# microcontroller_board2.net
KiCad netlist of a schematic drawn in Altium Designer
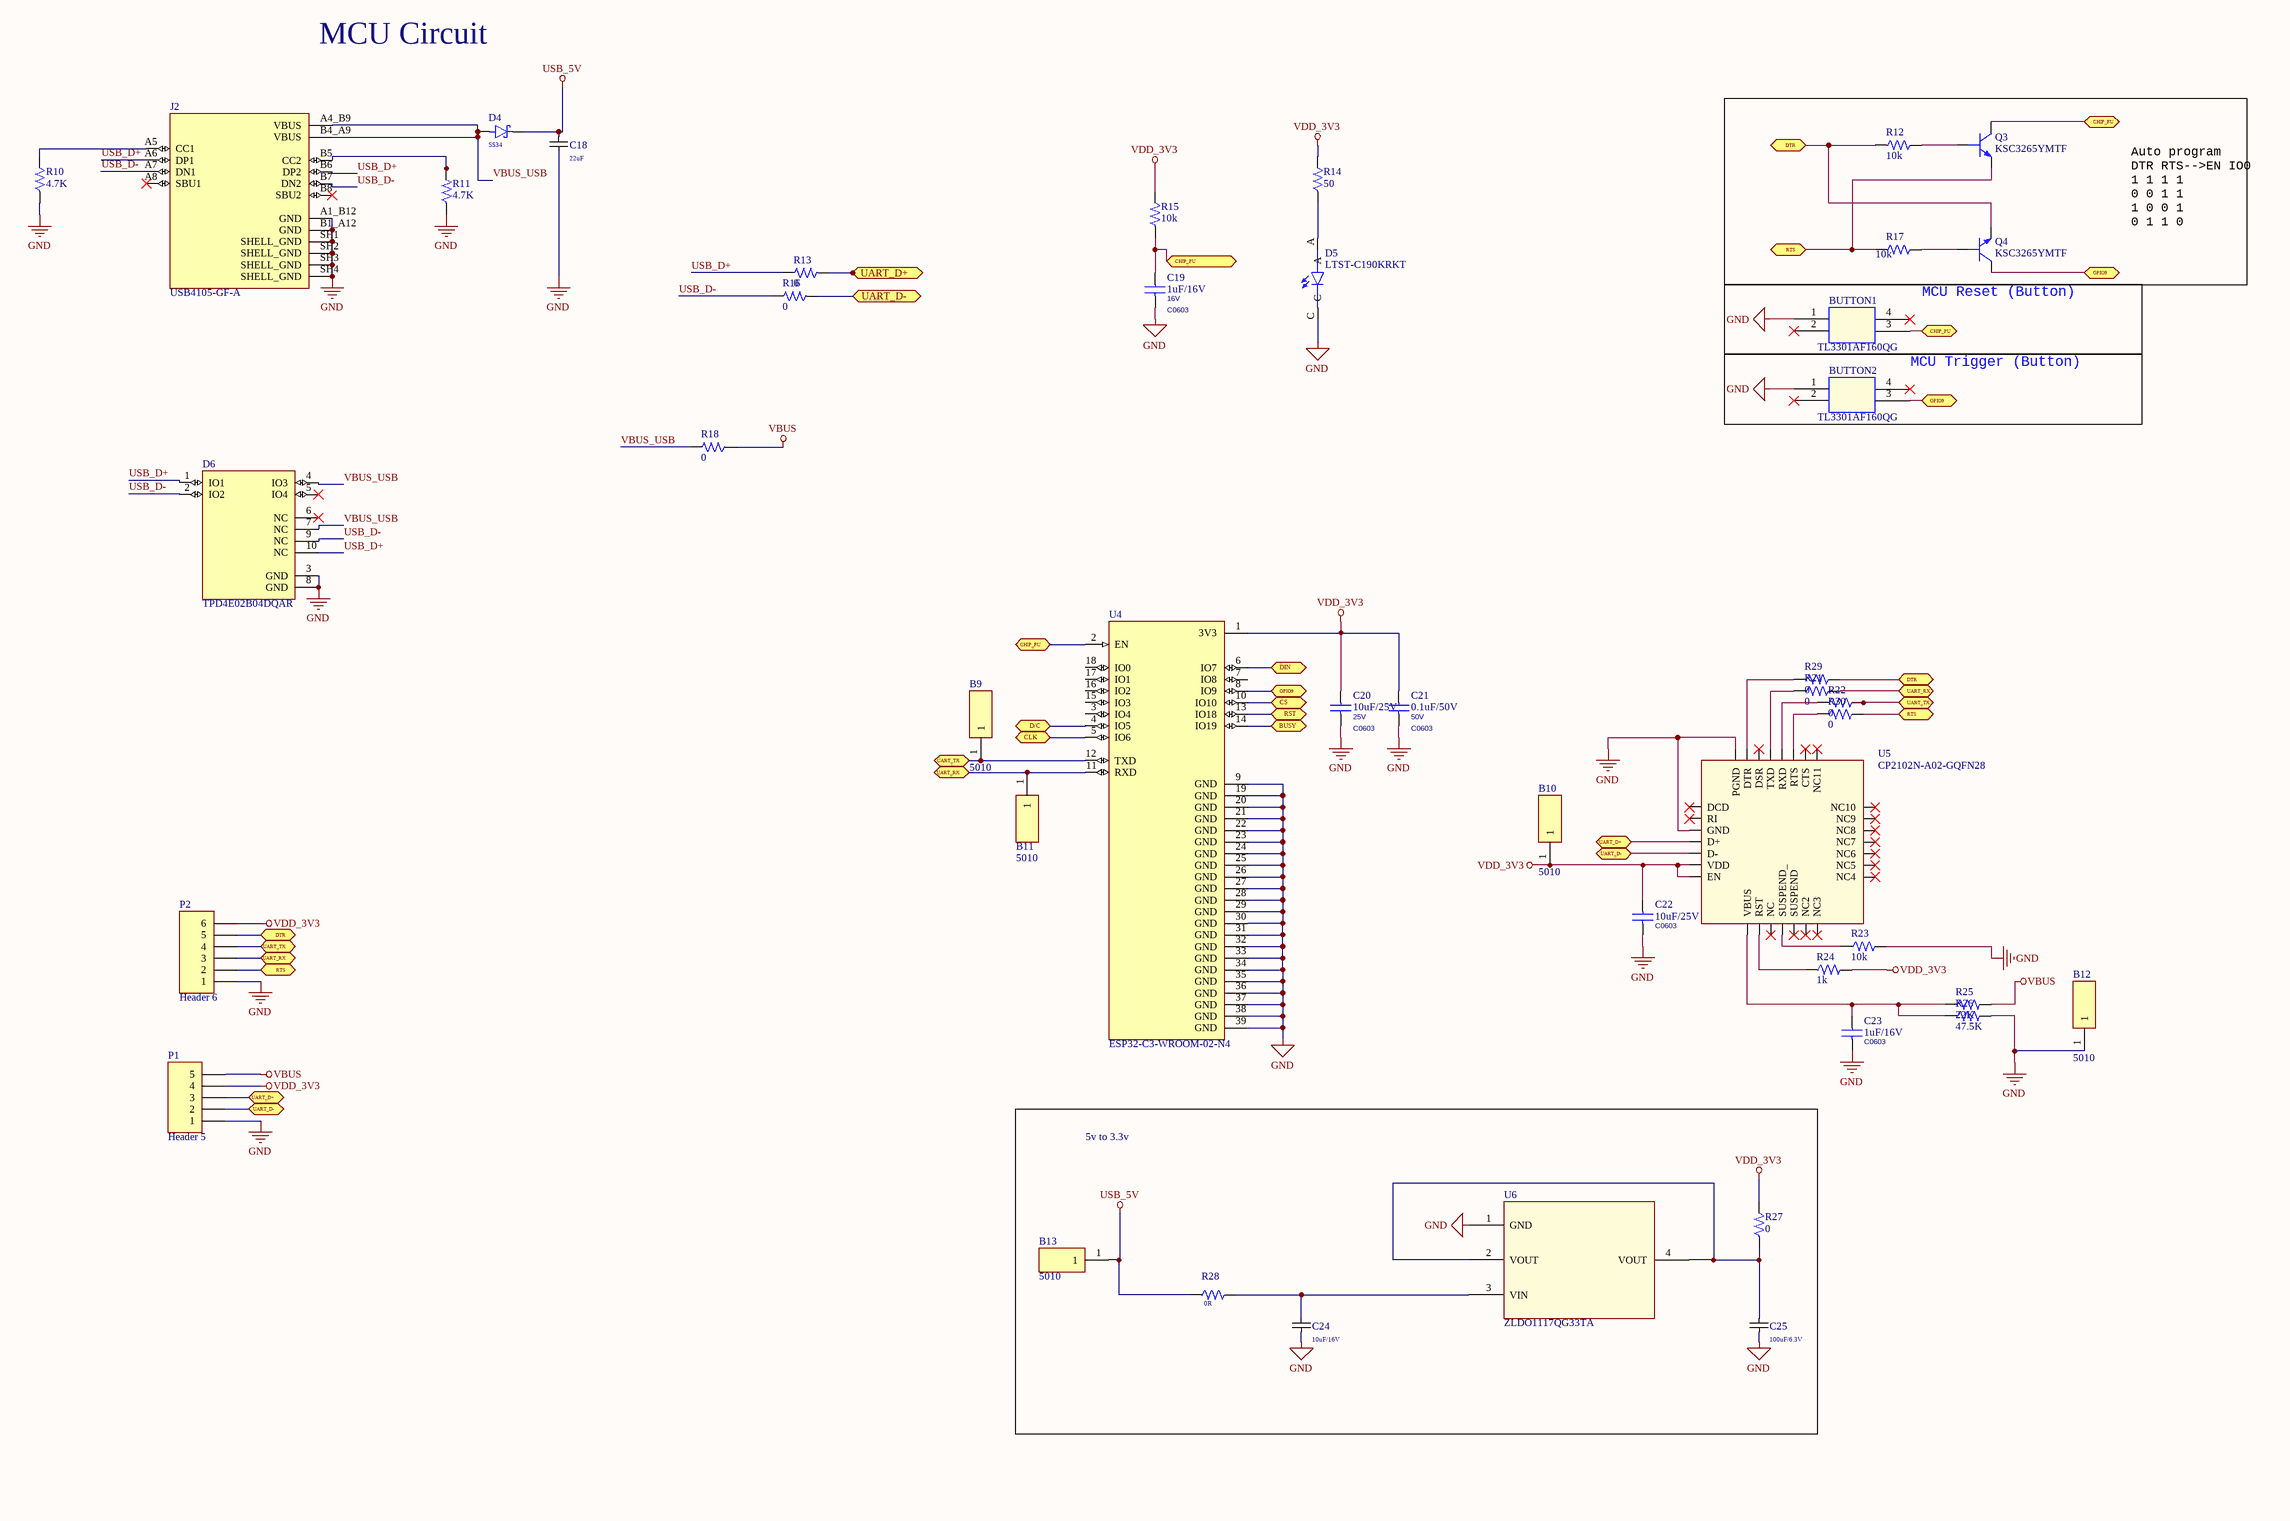
[diagram p0: microcontroller_board2.SchDoc]

(export (version "E")
  (design (tool "Eeschema 10.0.6"))
  (components
    (comp (ref "B9")
      (value "5010")
      (footprint "5010")
      (description "KEYSTONE - 5010 - TEST POINT, PCB, THROUGH HOLE")
      (fields (field (name "MOUSER PART NUMBER") "534-5010"))
      (libsource (lib "") (part "5010_1"))
    )
    (comp (ref "B10")
      (value "5010")
      (footprint "5010")
      (description "KEYSTONE - 5010 - TEST POINT, PCB, THROUGH HOLE")
      (fields (field (name "MOUSER PART NUMBER") "534-5010"))
      (libsource (lib "") (part "5010_1"))
    )
    (comp (ref "B11")
      (value "5010")
      (footprint "5010")
      (description "KEYSTONE - 5010 - TEST POINT, PCB, THROUGH HOLE")
      (fields (field (name "MOUSER PART NUMBER") "534-5010"))
      (libsource (lib "Schlib1") (part "5010"))
    )
    (comp (ref "B12")
      (value "5010")
      (footprint "5010")
      (description "KEYSTONE - 5010 - TEST POINT, PCB, THROUGH HOLE")
      (fields (field (name "MOUSER PART NUMBER") "534-5010"))
      (libsource (lib "") (part "5010_1"))
    )
    (comp (ref "B13")
      (value "5010")
      (footprint "5010")
      (description "KEYSTONE - 5010 - TEST POINT, PCB, THROUGH HOLE")
      (fields (field (name "MOUSER PART NUMBER") "534-5010"))
      (libsource (lib "R41") (part "5010"))
    )
    (comp (ref "BUTTON1")
      (value "TL3301AF160QG")
      (footprint "TL3301AF160QG")
      (libsource (lib "*") (part "CON4AP_0"))
    )
    (comp (ref "BUTTON2")
      (value "TL3301AF160QG")
      (footprint "TL3301AF160QG")
      (libsource (lib "*") (part "CON4AP_0"))
    )
    (comp (ref "C18")
      (value "22uF")
      (footprint "Cap_0805")
      (description "810-C2012X5R1V226MAC")
      (fields (field (name "MP") "C2012X5R1V226M125AC"))
      (libsource (lib "LRC_Components") (part "CAP_0805"))
    )
    (comp (ref "C19")
      (value "1uF/16V")
      (footprint "Cap_0603")
      (fields
        (field (name "PCB FOOTPRINT") "C0603")
        (field (name "PART NUMBER") "NC_0102-1422C12")
        (field (name "MANUFACTURER") "Murata")
        (field (name "TOLERANCE") "¡Ó10%")
        (field (name "VOLTAGE") "16V")
      )
      (libsource (lib "*") (part "CAP NP_Dup2"))
    )
    (comp (ref "C20")
      (value "10uF/25V")
      (footprint "Cap_0603")
      (fields
        (field (name "PART NUMBER") "NC_0102-1422C12")
        (field (name "MANUFACTURER") "Murata")
        (field (name "TOLERANCE") "¡Ó10%")
        (field (name "VOLTAGE") "25V")
        (field (name "PCB FOOTPRINT") "C0603")
      )
      (libsource (lib "*") (part "CAP NP_Dup2"))
    )
    (comp (ref "C21")
      (value "0.1uF/50V")
      (footprint "Cap_0603")
      (fields
        (field (name "PART NUMBER") "NC_0102-1422C12")
        (field (name "MANUFACTURER") "Murata")
        (field (name "TOLERANCE") "¡Ó10%")
        (field (name "VOLTAGE") "50V")
        (field (name "PCB FOOTPRINT") "C0603")
      )
      (libsource (lib "*") (part "CAP NP_Dup2"))
    )
    (comp (ref "C22")
      (value "10uF/25V")
      (footprint "Cap_0603")
      (description "GRM188R61E106MA73J")
      (fields
        (field (name "PCB FOOTPRINT") "C0603")
        (field (name "VOLTAGE") "16V")
        (field (name "TOLERANCE") "¡Ó10%")
      )
      (libsource (lib "*") (part "CAP NP_Dup2"))
    )
    (comp (ref "C23")
      (value "1uF/16V")
      (footprint "Cap_0603")
      (description "GRT188R71C105KE13D")
      (fields
        (field (name "PCB FOOTPRINT") "C0603")
        (field (name "VOLTAGE") "16V")
        (field (name "TOLERANCE") "¡Ó10%")
      )
      (libsource (lib "*") (part "CAP NP_Dup2"))
    )
    (comp (ref "C24")
      (value "10uF/16V")
      (footprint "Cap_0603")
      (description "C54")
      (fields (field (name "MP") "GRM188R61C106MAALD"))
      (libsource (lib "LRC_Components") (part "CAP_0603"))
    )
    (comp (ref "C25")
      (value "100uF/6.3V")
      (footprint "Cap_0805")
      (description "GRM21BR60J107ME15K")
      (libsource (lib "LRC_Components") (part "CAP_0805"))
    )
    (comp (ref "D4")
      (value "SS34")
      (footprint "DIOM7959X265N")
      (description "Diode Schottky 40 V 3A Surface Mount SMC (DO-214AB)")
      (fields (field (name "MF") "onsemi"))
      (libsource (lib "SS34") (part "SS34"))
    )
    (comp (ref "D5")
      (value "LTST-C190KRKT")
      (footprint "LEDM1608X80")
      (description "Red 626nm LED Indication - Discrete 2.1V 0603 _1608 Metric_")
      (fields (field (name "MF") "Broadcom Limited"))
      (libsource (lib "HSMS-C190") (part "HSMS-C190"))
    )
    (comp (ref "D6")
      (value "TPD4E02B04DQAR")
      (footprint "DIO_TPD4E02B04DQAR")
      (description "4-channel ESD protection diode for USB Type-C and HDMI 2.0 10-USON -40 to 125")
      (fields (field (name "MF") "Texas Instruments") (field (name "DIGI-KEY_PART_NUMBER") "296-43875-1-ND"))
      (libsource (lib "TPD4E02B04DQAR") (part "TPD4E02B04DQAR"))
    )
    (comp (ref "J2")
      (value "USB4105-GF-A")
      (footprint "GCT_USB4105-GF-A")
      (fields (field (name "MF") "GCT"))
      (libsource (lib "USB4105-GF-A") (part "USB4105-GF-A"))
    )
    (comp (ref "P1")
      (value "Header 5")
      (footprint "HDR1X5")
      (description "Header, 5-Pin")
      (fields (field (name "PUBLISHER") "Altium Limited"))
      (libsource (lib "Miscellaneous Connectors") (part "Header 5"))
    )
    (comp (ref "P2")
      (value "Header 6")
      (footprint "HDR1X6")
      (description "Header, 6-Pin")
      (fields (field (name "PUBLISHER") "Altium Limited"))
      (libsource (lib "Miscellaneous Connectors") (part "Header 6"))
    )
    (comp (ref "Q3")
      (value "KSC3265YMTF")
      (footprint "KSC3265YMTF")
      (description "Bipolar Transistors - BJT NPN Epitaxial Transistor")
      (libsource (lib "R41") (part "KSC3265YMTF"))
    )
    (comp (ref "Q4")
      (value "KSC3265YMTF")
      (footprint "KSC3265YMTF")
      (description "Bipolar Transistors - BJT NPN Epitaxial Transistor")
      (libsource (lib "R41") (part "KSC3265YMTF"))
    )
    (comp (ref "R10") (value "4.7K") (footprint "RES_0603") (libsource (lib "Schlib1") (part "RES_0603")))
    (comp (ref "R11") (value "4.7K") (footprint "RES_0603") (libsource (lib "Schlib1") (part "RES_0603")))
    (comp (ref "R12") (value "10k") (footprint "RES_0603") (libsource (lib "Schlib1") (part "RES_0603")))
    (comp (ref "R13")
      (value "0")
      (footprint "RES_0603")
      (fields (field (name "MP") "AC0603FR-070RL"))
      (libsource (lib "R41") (part "RES_0603"))
    )
    (comp (ref "R14")
      (value "50")
      (footprint "RES_0603")
      (fields (field (name "MP") "RT0603BRE0750RL"))
      (libsource (lib "R41") (part "RES_0603"))
    )
    (comp (ref "R15") (value "10k") (footprint "RES_0603") (libsource (lib "Schlib1") (part "RES_0603")))
    (comp (ref "R16")
      (value "0")
      (footprint "RES_0603")
      (fields (field (name "MP") "AC0603FR-070RL"))
      (libsource (lib "R41") (part "RES_0603"))
    )
    (comp (ref "R17") (value "10k") (footprint "RES_0603") (libsource (lib "Schlib1") (part "RES_0603")))
    (comp (ref "R18")
      (value "0")
      (footprint "RES_0603")
      (fields (field (name "MP") "AC0603FR-070RL"))
      (libsource (lib "R41") (part "RES_0603"))
    )
    (comp (ref "R21") (value "0") (footprint "RES_0603") (libsource (lib "Schlib1") (part "RES_0603")))
    (comp (ref "R22") (value "0") (footprint "RES_0603") (libsource (lib "Schlib1") (part "RES_0603")))
    (comp (ref "R23") (value "10k") (footprint "RES_0603") (libsource (lib "Schlib1") (part "RES_0603")))
    (comp (ref "R24") (value "1k") (footprint "RES_0603") (libsource (lib "Schlib1") (part "RES_0603")))
    (comp (ref "R25") (value "22K") (footprint "RES_0603") (libsource (lib "Schlib1") (part "RES_0603")))
    (comp (ref "R26") (value "47.5K") (footprint "RES_0603") (libsource (lib "Schlib1") (part "RES_0603")))
    (comp (ref "R27")
      (value "0")
      (footprint "RES_0603")
      (fields (field (name "MP") "AC0603FR-070RL"))
      (libsource (lib "R41") (part "RES_0603"))
    )
    (comp (ref "R28")
      (value "0R")
      (footprint "RES_0805")
      (description "RC0805JR-070RL")
      (libsource (lib "LRC_Components") (part "RES_0805"))
    )
    (comp (ref "R29") (value "0") (footprint "RES_0603") (libsource (lib "Schlib1") (part "RES_0603")))
    (comp (ref "R30") (value "0") (footprint "RES_0603") (libsource (lib "Schlib1") (part "RES_0603")))
    (comp (ref "U4")
      (value "ESP32-C3-WROOM-02-N4")
      (footprint "MODULE_ESP32-C3-WROOM-02-H4")
      (fields (field (name "MF") "Espressif Systems"))
      (libsource (lib "ESP32-C3-WROOM-02-N4") (part "ESP32-C3-WROOM-02-N4"))
    )
    (comp (ref "U5")
      (value "CP2102N-A02-GQFN28")
      (footprint "CP2102N-A02-GQFN28")
      (description "USB Interface IC USBXpress - USB to UART Bridge")
      (libsource (lib "R41") (part "CP2102N-A02-GQFN28"))
    )
    (comp (ref "U6")
      (value "ZLDO1117QG33TA")
      (footprint "ZLDO1117QG33TA")
      (libsource (lib "R41") (part "ZLDO1117QG33TA"))
    )
  )
  (nets
    (net (code "1") (name "/BUSY") (class "Default")
      (node (ref "U4") (pin "14") (pinfunction "IO19_14") (pintype "bidirectional"))
    )
    (net (code "2") (name "/CHIP_PU") (class "Default")
      (node (ref "BUTTON1") (pin "3") (pinfunction "+_3") (pintype "passive"))
      (node (ref "C19") (pin "1") (pinfunction "1_1") (pintype "passive"))
      (node (ref "Q3") (pin "3") (pinfunction "C_3") (pintype "passive"))
      (node (ref "R15") (pin "1") (pinfunction "1_1") (pintype "passive"))
      (node (ref "U4") (pin "2") (pinfunction "EN_2") (pintype "input"))
    )
    (net (code "3") (name "/CLK") (class "Default")
      (node (ref "U4") (pin "5") (pinfunction "IO6_5") (pintype "bidirectional"))
    )
    (net (code "4") (name "/CS") (class "Default")
      (node (ref "U4") (pin "10") (pinfunction "IO10_10") (pintype "bidirectional"))
    )
    (net (code "5") (name "/DIN") (class "Default")
      (node (ref "U4") (pin "6") (pinfunction "IO7_6") (pintype "bidirectional"))
    )
    (net (code "6") (name "/DTR") (class "Default")
      (node (ref "P2") (pin "5") (pinfunction "5_5") (pintype "passive"))
      (node (ref "Q4") (pin "2") (pinfunction "E_2") (pintype "passive"))
      (node (ref "R12") (pin "1") (pinfunction "1_1") (pintype "passive"))
      (node (ref "R29") (pin "2") (pinfunction "2_2") (pintype "passive"))
    )
    (net (code "7") (name "/D{slash}C") (class "Default")
      (node (ref "U4") (pin "4") (pinfunction "IO5_4") (pintype "bidirectional"))
    )
    (net (code "8") (name "/GPIO9") (class "Default")
      (node (ref "BUTTON2") (pin "3") (pinfunction "+_3") (pintype "passive"))
      (node (ref "Q4") (pin "3") (pinfunction "C_3") (pintype "passive"))
      (node (ref "U4") (pin "8") (pinfunction "IO9_8") (pintype "bidirectional"))
    )
    (net (code "9") (name "/RST") (class "Default")
      (node (ref "U4") (pin "13") (pinfunction "IO18_13") (pintype "bidirectional"))
    )
    (net (code "10") (name "/RTS") (class "Default")
      (node (ref "P2") (pin "2") (pinfunction "2_2") (pintype "passive"))
      (node (ref "Q3") (pin "2") (pinfunction "E_2") (pintype "passive"))
      (node (ref "R17") (pin "1") (pinfunction "1_1") (pintype "passive"))
      (node (ref "R30") (pin "2") (pinfunction "2_2") (pintype "passive"))
    )
    (net (code "11") (name "/UART_D+") (class "Default")
      (node (ref "P1") (pin "3") (pinfunction "3_3") (pintype "passive"))
      (node (ref "R13") (pin "1") (pinfunction "1_1") (pintype "passive"))
      (node (ref "U5") (pin "4") (pinfunction "D+_4") (pintype "passive"))
    )
    (net (code "12") (name "/UART_D-") (class "Default")
      (node (ref "P1") (pin "2") (pinfunction "2_2") (pintype "passive"))
      (node (ref "R16") (pin "1") (pinfunction "1_1") (pintype "passive"))
      (node (ref "U5") (pin "5") (pinfunction "D-_5") (pintype "passive"))
    )
    (net (code "13") (name "/UART_RX") (class "Default")
      (node (ref "B11") (pin "1") (pinfunction "1_1") (pintype "passive"))
      (node (ref "P2") (pin "3") (pinfunction "3_3") (pintype "passive"))
      (node (ref "R21") (pin "2") (pinfunction "2_2") (pintype "passive"))
      (node (ref "U4") (pin "11") (pinfunction "RXD_11") (pintype "bidirectional"))
    )
    (net (code "14") (name "/UART_TX") (class "Default")
      (node (ref "B9") (pin "1") (pinfunction "1_1") (pintype "passive"))
      (node (ref "P2") (pin "4") (pinfunction "4_4") (pintype "passive"))
      (node (ref "R22") (pin "2") (pinfunction "2_2") (pintype "passive"))
      (node (ref "U4") (pin "12") (pinfunction "TXD_12") (pintype "bidirectional"))
    )
    (net (code "15") (name "/USB_D+") (class "Default")
      (node (ref "D6") (pin "1") (pinfunction "IO1_1") (pintype "bidirectional"))
      (node (ref "D6") (pin "10") (pinfunction "NC_10") (pintype "passive"))
      (node (ref "J2") (pin "A6") (pinfunction "DP1_A6") (pintype "bidirectional"))
      (node (ref "J2") (pin "B6") (pinfunction "DP2_B6") (pintype "bidirectional"))
      (node (ref "R13") (pin "2") (pinfunction "2_2") (pintype "passive"))
    )
    (net (code "16") (name "/USB_D-") (class "Default")
      (node (ref "D6") (pin "2") (pinfunction "IO2_2") (pintype "bidirectional"))
      (node (ref "D6") (pin "9") (pinfunction "NC_9") (pintype "passive"))
      (node (ref "J2") (pin "A7") (pinfunction "DN1_A7") (pintype "bidirectional"))
      (node (ref "J2") (pin "B7") (pinfunction "DN2_B7") (pintype "bidirectional"))
      (node (ref "R16") (pin "2") (pinfunction "2_2") (pintype "passive"))
    )
    (net (code "17") (name "/VBUS_USB") (class "Default")
      (node (ref "D4") (pin "A") (pinfunction "A_A") (pintype "passive"))
      (node (ref "D6") (pin "4") (pinfunction "IO3_4") (pintype "bidirectional"))
      (node (ref "D6") (pin "7") (pinfunction "NC_7") (pintype "passive"))
      (node (ref "J2") (pin "A4_B9") (pinfunction "VBUS_A4_B9") (pintype "power_in"))
      (node (ref "J2") (pin "B4_A9") (pinfunction "VBUS_B4_A9") (pintype "power_in"))
      (node (ref "R18") (pin "2") (pinfunction "2_2") (pintype "passive"))
    )
    (net (code "18") (name "GND") (class "Default")
      (node (ref "B12") (pin "1") (pinfunction "1_1") (pintype "passive"))
      (node (ref "BUTTON1") (pin "1") (pinfunction "+_1") (pintype "passive"))
      (node (ref "BUTTON2") (pin "1") (pinfunction "+_1") (pintype "passive"))
      (node (ref "C18") (pin "1") (pintype "passive"))
      (node (ref "C19") (pin "2") (pinfunction "2_2") (pintype "passive"))
      (node (ref "C20") (pin "2") (pinfunction "2_2") (pintype "passive"))
      (node (ref "C21") (pin "2") (pinfunction "2_2") (pintype "passive"))
      (node (ref "C22") (pin "2") (pinfunction "2_2") (pintype "passive"))
      (node (ref "C23") (pin "2") (pinfunction "2_2") (pintype "passive"))
      (node (ref "C24") (pin "1") (pintype "passive"))
      (node (ref "C25") (pin "1") (pintype "passive"))
      (node (ref "D5") (pin "C") (pinfunction "C_C") (pintype "passive"))
      (node (ref "D6") (pin "3") (pinfunction "GND_3") (pintype "power_in"))
      (node (ref "D6") (pin "8") (pinfunction "GND_8") (pintype "power_in"))
      (node (ref "J2") (pin "A1_B12") (pinfunction "GND_A1_B12") (pintype "power_in"))
      (node (ref "J2") (pin "B1_A12") (pinfunction "GND_B1_A12") (pintype "power_in"))
      (node (ref "J2") (pin "SH1") (pinfunction "SHELL_GND_SH1") (pintype "power_in"))
      (node (ref "J2") (pin "SH2") (pinfunction "SHELL_GND_SH2") (pintype "power_in"))
      (node (ref "J2") (pin "SH3") (pinfunction "SHELL_GND_SH3") (pintype "power_in"))
      (node (ref "J2") (pin "SH4") (pinfunction "SHELL_GND_SH4") (pintype "power_in"))
      (node (ref "P1") (pin "1") (pinfunction "1_1") (pintype "passive"))
      (node (ref "P2") (pin "1") (pinfunction "1_1") (pintype "passive"))
      (node (ref "R10") (pin "1") (pinfunction "1_1") (pintype "passive"))
      (node (ref "R11") (pin "1") (pinfunction "1_1") (pintype "passive"))
      (node (ref "R23") (pin "2") (pinfunction "2_2") (pintype "passive"))
      (node (ref "R26") (pin "2") (pinfunction "2_2") (pintype "passive"))
      (node (ref "U4") (pin "19") (pinfunction "GND_19") (pintype "power_in"))
      (node (ref "U4") (pin "20") (pinfunction "GND_20") (pintype "power_in"))
      (node (ref "U4") (pin "21") (pinfunction "GND_21") (pintype "power_in"))
      (node (ref "U4") (pin "22") (pinfunction "GND_22") (pintype "power_in"))
      (node (ref "U4") (pin "23") (pinfunction "GND_23") (pintype "power_in"))
      (node (ref "U4") (pin "24") (pinfunction "GND_24") (pintype "power_in"))
      (node (ref "U4") (pin "25") (pinfunction "GND_25") (pintype "power_in"))
      (node (ref "U4") (pin "26") (pinfunction "GND_26") (pintype "power_in"))
      (node (ref "U4") (pin "27") (pinfunction "GND_27") (pintype "power_in"))
      (node (ref "U4") (pin "28") (pinfunction "GND_28") (pintype "power_in"))
      (node (ref "U4") (pin "29") (pinfunction "GND_29") (pintype "power_in"))
      (node (ref "U4") (pin "30") (pinfunction "GND_30") (pintype "power_in"))
      (node (ref "U4") (pin "31") (pinfunction "GND_31") (pintype "power_in"))
      (node (ref "U4") (pin "32") (pinfunction "GND_32") (pintype "power_in"))
      (node (ref "U4") (pin "33") (pinfunction "GND_33") (pintype "power_in"))
      (node (ref "U4") (pin "34") (pinfunction "GND_34") (pintype "power_in"))
      (node (ref "U4") (pin "35") (pinfunction "GND_35") (pintype "power_in"))
      (node (ref "U4") (pin "36") (pinfunction "GND_36") (pintype "power_in"))
      (node (ref "U4") (pin "37") (pinfunction "GND_37") (pintype "power_in"))
      (node (ref "U4") (pin "38") (pinfunction "GND_38") (pintype "power_in"))
      (node (ref "U4") (pin "39") (pinfunction "GND_39") (pintype "power_in"))
      (node (ref "U4") (pin "9") (pinfunction "GND_9") (pintype "power_in"))
      (node (ref "U5") (pin "29") (pinfunction "PGND_29") (pintype "passive"))
      (node (ref "U5") (pin "3") (pinfunction "GND_3") (pintype "passive"))
      (node (ref "U6") (pin "1") (pinfunction "GND_1") (pintype "passive"))
    )
    (net (code "19") (name "Net-(C25-Pad2)") (class "Default")
      (node (ref "C25") (pin "2") (pintype "passive"))
      (node (ref "R27") (pin "1") (pinfunction "1_1") (pintype "passive"))
      (node (ref "U6") (pin "2") (pinfunction "VOUT_2") (pintype "passive"))
      (node (ref "U6") (pin "4") (pinfunction "VOUT_4") (pintype "passive"))
    )
    (net (code "20") (name "Net-(D5-PadA)") (class "Default")
      (node (ref "D5") (pin "A") (pinfunction "A_A") (pintype "passive"))
      (node (ref "R14") (pin "1") (pinfunction "1_1") (pintype "passive"))
    )
    (net (code "21") (name "Net-(J2-CC1)") (class "Default")
      (node (ref "J2") (pin "A5") (pinfunction "CC1_A5") (pintype "bidirectional"))
      (node (ref "R10") (pin "2") (pinfunction "2_2") (pintype "passive"))
    )
    (net (code "22") (name "Net-(J2-CC2)") (class "Default")
      (node (ref "J2") (pin "B5") (pinfunction "CC2_B5") (pintype "bidirectional"))
      (node (ref "R11") (pin "2") (pinfunction "2_2") (pintype "passive"))
    )
    (net (code "23") (name "Net-(Q3-B)") (class "Default")
      (node (ref "Q3") (pin "1") (pinfunction "B_1") (pintype "passive"))
      (node (ref "R12") (pin "2") (pinfunction "2_2") (pintype "passive"))
    )
    (net (code "24") (name "Net-(Q4-B)") (class "Default")
      (node (ref "Q4") (pin "1") (pinfunction "B_1") (pintype "passive"))
      (node (ref "R17") (pin "2") (pinfunction "2_2") (pintype "passive"))
    )
    (net (code "25") (name "Net-(U5-DTR)") (class "Default")
      (node (ref "R29") (pin "1") (pinfunction "1_1") (pintype "passive"))
      (node (ref "U5") (pin "28") (pinfunction "DTR_28") (pintype "passive"))
    )
    (net (code "26") (name "Net-(U5-RST)") (class "Default")
      (node (ref "R24") (pin "1") (pinfunction "1_1") (pintype "passive"))
      (node (ref "U5") (pin "9") (pinfunction "RST_9") (pintype "passive"))
    )
    (net (code "27") (name "Net-(U5-RTS)") (class "Default")
      (node (ref "R30") (pin "1") (pinfunction "1_1") (pintype "passive"))
      (node (ref "U5") (pin "24") (pinfunction "RTS_24") (pintype "passive"))
    )
    (net (code "28") (name "Net-(U5-RXD)") (class "Default")
      (node (ref "R22") (pin "1") (pinfunction "1_1") (pintype "passive"))
      (node (ref "U5") (pin "25") (pinfunction "RXD_25") (pintype "passive"))
    )
    (net (code "29") (name "Net-(U5-SUSPEND_)") (class "Default")
      (node (ref "R23") (pin "1") (pinfunction "1_1") (pintype "passive"))
      (node (ref "U5") (pin "11") (pinfunction "SUSPEND__11") (pintype "passive"))
    )
    (net (code "30") (name "Net-(U5-TXD)") (class "Default")
      (node (ref "R21") (pin "1") (pinfunction "1_1") (pintype "passive"))
      (node (ref "U5") (pin "26") (pinfunction "TXD_26") (pintype "passive"))
    )
    (net (code "31") (name "Net-(U5-VBUS)") (class "Default")
      (node (ref "C23") (pin "1") (pinfunction "1_1") (pintype "passive"))
      (node (ref "R25") (pin "1") (pinfunction "1_1") (pintype "passive"))
      (node (ref "R26") (pin "1") (pinfunction "1_1") (pintype "passive"))
      (node (ref "U5") (pin "8") (pinfunction "VBUS_8") (pintype "passive"))
    )
    (net (code "32") (name "Net-(U6-VIN)") (class "Default")
      (node (ref "C24") (pin "2") (pintype "passive"))
      (node (ref "R28") (pin "2") (pinfunction "2_2") (pintype "passive"))
      (node (ref "U6") (pin "3") (pinfunction "VIN_3") (pintype "passive"))
    )
    (net (code "33") (name "USB_5V") (class "Default")
      (node (ref "B13") (pin "1") (pinfunction "1_1") (pintype "passive"))
      (node (ref "C18") (pin "2") (pintype "passive"))
      (node (ref "D4") (pin "C") (pinfunction "K_C") (pintype "passive"))
      (node (ref "R28") (pin "1") (pinfunction "1_1") (pintype "passive"))
    )
    (net (code "34") (name "VBUS") (class "Default")
      (node (ref "P1") (pin "5") (pinfunction "5_5") (pintype "passive"))
      (node (ref "R18") (pin "1") (pinfunction "1_1") (pintype "passive"))
      (node (ref "R25") (pin "2") (pinfunction "2_2") (pintype "passive"))
    )
    (net (code "35") (name "VDD_3V3") (class "Default")
      (node (ref "B10") (pin "1") (pinfunction "1_1") (pintype "passive"))
      (node (ref "C20") (pin "1") (pinfunction "1_1") (pintype "passive"))
      (node (ref "C21") (pin "1") (pinfunction "1_1") (pintype "passive"))
      (node (ref "C22") (pin "1") (pinfunction "1_1") (pintype "passive"))
      (node (ref "P1") (pin "4") (pinfunction "4_4") (pintype "passive"))
      (node (ref "P2") (pin "6") (pinfunction "6_6") (pintype "passive"))
      (node (ref "R14") (pin "2") (pinfunction "2_2") (pintype "passive"))
      (node (ref "R15") (pin "2") (pinfunction "2_2") (pintype "passive"))
      (node (ref "R24") (pin "2") (pinfunction "2_2") (pintype "passive"))
      (node (ref "R27") (pin "2") (pinfunction "2_2") (pintype "passive"))
      (node (ref "U4") (pin "1") (pinfunction "3V3_1") (pintype "power_in"))
      (node (ref "U5") (pin "6") (pinfunction "VDD_6") (pintype "passive"))
      (node (ref "U5") (pin "7") (pinfunction "EN_7") (pintype "passive"))
    )
    (net (code "36") (name "unconnected-(BUTTON1-+-Pad2)") (class "Default")
      (node (ref "BUTTON1") (pin "2") (pinfunction "+_2") (pintype "passive+no_connect"))
    )
    (net (code "37") (name "unconnected-(BUTTON1-+-Pad4)") (class "Default")
      (node (ref "BUTTON1") (pin "4") (pinfunction "+_4") (pintype "passive+no_connect"))
    )
    (net (code "38") (name "unconnected-(BUTTON2-+-Pad2)") (class "Default")
      (node (ref "BUTTON2") (pin "2") (pinfunction "+_2") (pintype "passive+no_connect"))
    )
    (net (code "39") (name "unconnected-(BUTTON2-+-Pad4)") (class "Default")
      (node (ref "BUTTON2") (pin "4") (pinfunction "+_4") (pintype "passive+no_connect"))
    )
    (net (code "40") (name "unconnected-(D6-IO4-Pad5)") (class "Default")
      (node (ref "D6") (pin "5") (pinfunction "IO4_5") (pintype "bidirectional+no_connect"))
    )
    (net (code "41") (name "unconnected-(D6-NC-Pad6)") (class "Default")
      (node (ref "D6") (pin "6") (pinfunction "NC_6") (pintype "passive+no_connect"))
    )
    (net (code "42") (name "unconnected-(J2-SBU1-PadA8)") (class "Default")
      (node (ref "J2") (pin "A8") (pinfunction "SBU1_A8") (pintype "bidirectional+no_connect"))
    )
    (net (code "43") (name "unconnected-(J2-SBU2-PadB8)") (class "Default")
      (node (ref "J2") (pin "B8") (pinfunction "SBU2_B8") (pintype "bidirectional+no_connect"))
    )
    (net (code "44") (name "unconnected-(U4-IO0-Pad18)") (class "Default")
      (node (ref "U4") (pin "18") (pinfunction "IO0_18") (pintype "bidirectional"))
    )
    (net (code "45") (name "unconnected-(U4-IO1-Pad17)") (class "Default")
      (node (ref "U4") (pin "17") (pinfunction "IO1_17") (pintype "bidirectional"))
    )
    (net (code "46") (name "unconnected-(U4-IO2-Pad16)") (class "Default")
      (node (ref "U4") (pin "16") (pinfunction "IO2_16") (pintype "bidirectional"))
    )
    (net (code "47") (name "unconnected-(U4-IO3-Pad15)") (class "Default")
      (node (ref "U4") (pin "15") (pinfunction "IO3_15") (pintype "bidirectional"))
    )
    (net (code "48") (name "unconnected-(U4-IO4-Pad3)") (class "Default")
      (node (ref "U4") (pin "3") (pinfunction "IO4_3") (pintype "bidirectional"))
    )
    (net (code "49") (name "unconnected-(U4-IO8-Pad7)") (class "Default")
      (node (ref "U4") (pin "7") (pinfunction "IO8_7") (pintype "bidirectional"))
    )
    (net (code "50") (name "unconnected-(U5-CTS-Pad23)") (class "Default")
      (node (ref "U5") (pin "23") (pinfunction "CTS_23") (pintype "passive+no_connect"))
    )
    (net (code "51") (name "unconnected-(U5-DCD-Pad1)") (class "Default")
      (node (ref "U5") (pin "1") (pinfunction "DCD_1") (pintype "passive+no_connect"))
    )
    (net (code "52") (name "unconnected-(U5-DSR-Pad27)") (class "Default")
      (node (ref "U5") (pin "27") (pinfunction "DSR_27") (pintype "passive+no_connect"))
    )
    (net (code "53") (name "unconnected-(U5-NC-Pad10)") (class "Default")
      (node (ref "U5") (pin "10") (pinfunction "NC_10") (pintype "passive+no_connect"))
    )
    (net (code "54") (name "unconnected-(U5-NC2-Pad13)") (class "Default")
      (node (ref "U5") (pin "13") (pinfunction "NC2_13") (pintype "passive+no_connect"))
    )
    (net (code "55") (name "unconnected-(U5-NC3-Pad14)") (class "Default")
      (node (ref "U5") (pin "14") (pinfunction "NC3_14") (pintype "passive+no_connect"))
    )
    (net (code "56") (name "unconnected-(U5-NC4-Pad15)") (class "Default")
      (node (ref "U5") (pin "15") (pinfunction "NC4_15") (pintype "passive+no_connect"))
    )
    (net (code "57") (name "unconnected-(U5-NC5-Pad16)") (class "Default")
      (node (ref "U5") (pin "16") (pinfunction "NC5_16") (pintype "passive+no_connect"))
    )
    (net (code "58") (name "unconnected-(U5-NC6-Pad17)") (class "Default")
      (node (ref "U5") (pin "17") (pinfunction "NC6_17") (pintype "passive+no_connect"))
    )
    (net (code "59") (name "unconnected-(U5-NC7-Pad18)") (class "Default")
      (node (ref "U5") (pin "18") (pinfunction "NC7_18") (pintype "passive+no_connect"))
    )
    (net (code "60") (name "unconnected-(U5-NC8-Pad19)") (class "Default")
      (node (ref "U5") (pin "19") (pinfunction "NC8_19") (pintype "passive+no_connect"))
    )
    (net (code "61") (name "unconnected-(U5-NC9-Pad20)") (class "Default")
      (node (ref "U5") (pin "20") (pinfunction "NC9_20") (pintype "passive+no_connect"))
    )
    (net (code "62") (name "unconnected-(U5-NC10-Pad21)") (class "Default")
      (node (ref "U5") (pin "21") (pinfunction "NC10_21") (pintype "passive+no_connect"))
    )
    (net (code "63") (name "unconnected-(U5-NC11-Pad22)") (class "Default")
      (node (ref "U5") (pin "22") (pinfunction "NC11_22") (pintype "passive+no_connect"))
    )
    (net (code "64") (name "unconnected-(U5-RI-Pad2)") (class "Default")
      (node (ref "U5") (pin "2") (pinfunction "RI_2") (pintype "passive+no_connect"))
    )
    (net (code "65") (name "unconnected-(U5-SUSPEND-Pad12)") (class "Default")
      (node (ref "U5") (pin "12") (pinfunction "SUSPEND_12") (pintype "passive+no_connect"))
    )
  )
)
